# Sheet1.net
KiCad netlist of a schematic drawn in Altium Designer
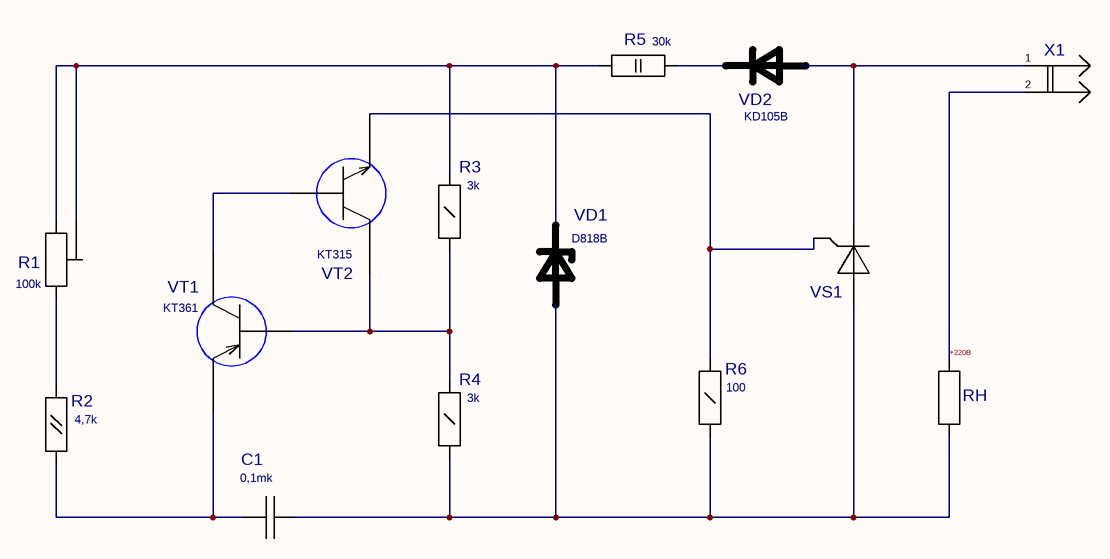
[diagram p0: Sheet1.SCHDOC]

(export (version "E")
  (design (tool "Eeschema 10.0.6"))
  (components
    (comp (ref "C1")
      (value "0,1mk")
      (footprint "K73-11-160В-4,7МКФ")
      (description "К73-11-160В-4,7МКФ")
      (libsource (lib "*") (part "К73-11-160В-4,7МКФ"))
    )
    (comp (ref "R1")
      (value "100k")
      (footprint "3006P")
      (description "3006W")
      (libsource (lib "*") (part "3006W"))
    )
    (comp (ref "R2")
      (value "4,7k")
      (footprint "C2-33H-0.125W")
      (description "C2-33H-0.125W_OLD_UGO")
      (fields (field (name "AUTOR") "pcbdesigner.ru"))
      (libsource (lib "*") (part "C2-33H-0.125W_OLD_UGO"))
    )
    (comp (ref "R3")
      (value "3k")
      (footprint "C2-33H-0.25W")
      (description "C2-33H-0.25W_OLD_UGO")
      (fields (field (name "AUTOR") "pcbdesigner.ru"))
      (libsource (lib "*") (part "C2-33H-0.25W_OLD_UGO"))
    )
    (comp (ref "R4")
      (value "3k")
      (footprint "C2-33H-0.25W")
      (description "C2-33H-0.25W_OLD_UGO")
      (fields (field (name "AUTOR") "pcbdesigner.ru"))
      (libsource (lib "*") (part "C2-33H-0.25W_OLD_UGO"))
    )
    (comp (ref "R5")
      (value "30k")
      (footprint "C2-33H-2W")
      (description "C2-33H-2W_OLD_UGO")
      (fields (field (name "AUTOR") "pcbdesigner.ru"))
      (libsource (lib "*") (part "C2-33H-2W_OLD_UGO"))
    )
    (comp (ref "R6")
      (value "100")
      (footprint "C2-33H-0.25W")
      (description "C2-33H-0.25W_OLD_UGO")
      (fields (field (name "AUTOR") "pcbdesigner.ru"))
      (libsource (lib "*") (part "C2-33H-0.25W_OLD_UGO"))
    )
    (comp (ref "RH")
      (value "C2-33Н-0.125W_10ММ")
      (footprint "C2-33H-0.125W_10MM")
      (libsource (lib "*") (part "C2-33Н-0.125W_10ММ"))
    )
    (comp (ref "VD1")
      (value "D818B")
      (footprint "Д818")
      (description "Д818А")
      (libsource (lib "*") (part "Д818А"))
    )
    (comp (ref "VD2")
      (value "KD105B")
      (footprint "КД105")
      (description "КД105Б")
      (libsource (lib "*") (part "КД105Б"))
    )
    (comp (ref "VS1") (value "KU202R") (footprint "KU202R") (libsource (lib "*") (part "KU202R")))
    (comp (ref "VT1")
      (value "KT361")
      (footprint "KT13")
      (description "КТ361А")
      (libsource (lib "*") (part "КТ361А"))
    )
    (comp (ref "VT2")
      (value "KT315")
      (footprint "KT13")
      (description "КТ315А")
      (libsource (lib "*") (part "КТ315А"))
    )
    (comp (ref "X1") (value "PW15-2M") (footprint "PW15-2M") (libsource (lib "*") (part "PW15-2M")))
  )
  (nets
    (net (code "1") (name "/+220B") (class "Default")
      (node (ref "RH") (pin "2") (pinfunction "2_2") (pintype "passive"))
      (node (ref "X1") (pin "2") (pinfunction "I/O2_2") (pintype "passive"))
    )
    (net (code "2") (name "Net-(R1-Pad1)") (class "Default")
      (node (ref "R1") (pin "1") (pinfunction "1_1") (pintype "passive"))
      (node (ref "R2") (pin "2") (pinfunction "2_2") (pintype "passive"))
    )
    (net (code "3") (name "Net-(R1-Pad2)") (class "Default")
      (node (ref "R1") (pin "2") (pinfunction "2_2") (pintype "passive"))
      (node (ref "R1") (pin "3") (pinfunction "3_3") (pintype "passive"))
      (node (ref "R3") (pin "2") (pinfunction "2_2") (pintype "passive"))
      (node (ref "R5") (pin "1") (pinfunction "1_1") (pintype "passive"))
      (node (ref "VD1") (pin "K") (pinfunction "K_K") (pintype "passive"))
    )
    (net (code "4") (name "Net-(R5-Pad2)") (class "Default")
      (node (ref "R5") (pin "2") (pinfunction "2_2") (pintype "passive"))
      (node (ref "VD2") (pin "K") (pinfunction "K_K") (pintype "passive"))
    )
    (net (code "5") (name "Net-(VS1-IN)") (class "Default")
      (node (ref "R6") (pin "2") (pinfunction "2_2") (pintype "passive"))
      (node (ref "VS1") (pin "3") (pinfunction "IN_3") (pintype "passive"))
      (node (ref "VT2") (pin "1") (pinfunction "E_1") (pintype "passive"))
    )
    (net (code "6") (name "Net-(VS1-I{slash}OA)") (class "Default")
      (node (ref "C1") (pin "2") (pinfunction "2_2") (pintype "passive"))
      (node (ref "R4") (pin "1") (pinfunction "1_1") (pintype "passive"))
      (node (ref "R6") (pin "1") (pinfunction "1_1") (pintype "passive"))
      (node (ref "RH") (pin "1") (pinfunction "1_1") (pintype "passive"))
      (node (ref "VD1") (pin "A") (pinfunction "A_A") (pintype "passive"))
      (node (ref "VS1") (pin "1") (pinfunction "I/OA_1") (pintype "passive"))
    )
    (net (code "7") (name "Net-(VS1-I{slash}OB)") (class "Default")
      (node (ref "VD2") (pin "A") (pinfunction "A_A") (pintype "passive"))
      (node (ref "VS1") (pin "2") (pinfunction "I/OB_2") (pintype "passive"))
      (node (ref "X1") (pin "1") (pinfunction "I/O1_1") (pintype "passive"))
    )
    (net (code "8") (name "Net-(VT1-B)") (class "Default")
      (node (ref "R3") (pin "1") (pinfunction "1_1") (pintype "passive"))
      (node (ref "R4") (pin "2") (pinfunction "2_2") (pintype "passive"))
      (node (ref "VT1") (pin "2") (pinfunction "B_2") (pintype "passive"))
      (node (ref "VT2") (pin "3") (pinfunction "K_3") (pintype "passive"))
    )
    (net (code "9") (name "Net-(VT1-E)") (class "Default")
      (node (ref "C1") (pin "1") (pinfunction "1_1") (pintype "passive"))
      (node (ref "R2") (pin "1") (pinfunction "1_1") (pintype "passive"))
      (node (ref "VT1") (pin "1") (pinfunction "E_1") (pintype "passive"))
    )
    (net (code "10") (name "Net-(VT1-K)") (class "Default")
      (node (ref "VT1") (pin "3") (pinfunction "K_3") (pintype "passive"))
      (node (ref "VT2") (pin "2") (pinfunction "B_2") (pintype "passive"))
    )
    (net (code "11") (name "unconnected-(VS1-Pad4)") (class "Default")
      (node (ref "VS1") (pin "4") (pintype "passive"))
    )
    (net (code "12") (name "unconnected-(VS1-Pad5)") (class "Default")
      (node (ref "VS1") (pin "5") (pintype "passive"))
    )
  )
)
